# CMoy_breadboard.net
KiCad netlist of a schematic drawn in Altium Designer
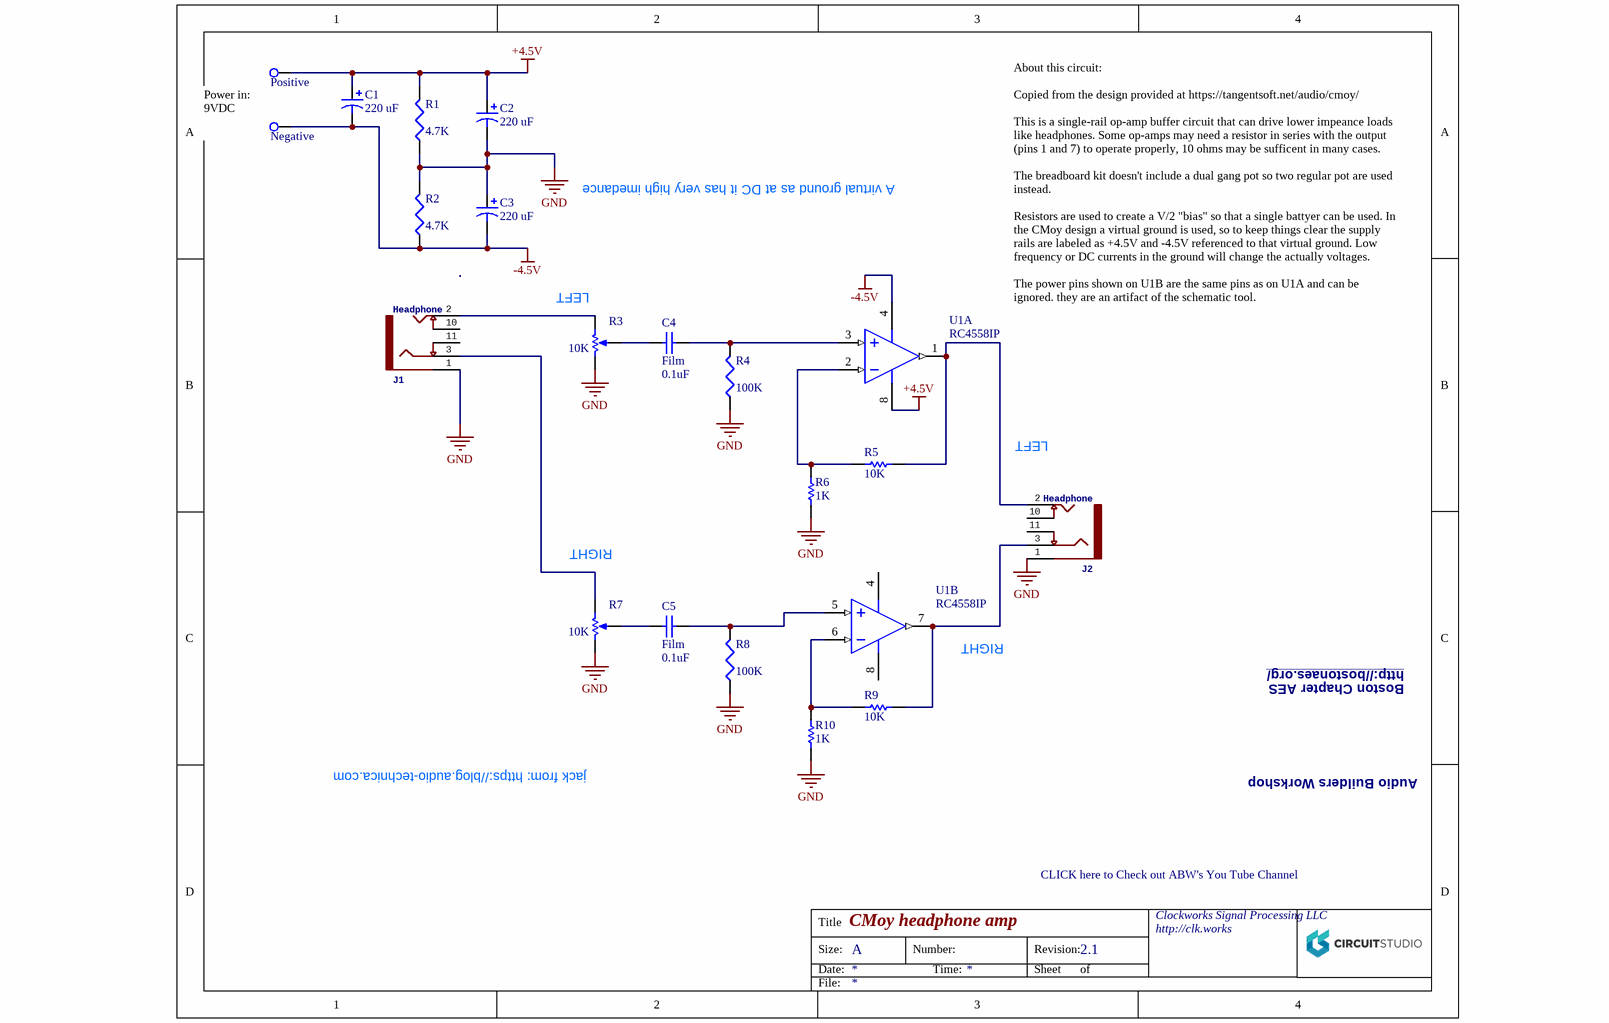
[diagram p0: CMoy.breadboard.SchDoc]

(export (version "E")
  (design (tool "Eeschema 10.0.6"))
  (components
    (comp (ref "C1")
      (value "220 uF")
      (footprint "RB7.6-15")
      (description "Polarized Capacitor (Radial)")
      (fields (field (name "Comment") "Cap Pol1") (field (name "PUBLISHER") "Altium Limited"))
      (libsource (lib "Miscellaneous Devices") (part "Cap Pol1"))
    )
    (comp (ref "C2")
      (value "220 uF")
      (footprint "RB7.6-15")
      (description "Polarized Capacitor (Radial)")
      (fields (field (name "Comment") "Cap Pol1") (field (name "PUBLISHER") "Altium Limited"))
      (libsource (lib "Miscellaneous Devices") (part "Cap Pol1"))
    )
    (comp (ref "C3")
      (value "220 uF")
      (footprint "RB7.6-15")
      (description "Polarized Capacitor (Radial)")
      (fields (field (name "Comment") "Cap Pol1") (field (name "PUBLISHER") "Altium Limited"))
      (libsource (lib "Miscellaneous Devices") (part "Cap Pol1"))
    )
    (comp (ref "C4")
      (value "Film")
      (footprint "RAD-0.3")
      (description "Capacitor")
      (fields (field (name "ALTIUM_VALUE") "0.1uF") (field (name "PUBLISHER") "Altium Limited"))
      (libsource (lib "Miscellaneous Devices") (part "Cap"))
    )
    (comp (ref "C5")
      (value "Film")
      (footprint "RAD-0.3")
      (description "Capacitor")
      (fields (field (name "ALTIUM_VALUE") "0.1uF") (field (name "PUBLISHER") "Altium Limited"))
      (libsource (lib "Miscellaneous Devices") (part "Cap"))
    )
    (comp (ref "J1")
      (value "Headphone")
      (footprint "SWITCHCRAFT_35RAPC4BHN2")
      (description "Conn 3.5MM Stereo Jack F 5 POS Solder RA Thru-Hole 5 Terminal 1 Port")
      (libsource (lib "CSP.J.connectors") (part "CSP-J0022-A"))
    )
    (comp (ref "J2")
      (value "Headphone")
      (footprint "SWITCHCRAFT_35RAPC4BHN2")
      (description "Conn 3.5MM Stereo Jack F 5 POS Solder RA Thru-Hole 5 Terminal 1 Port")
      (libsource (lib "") (part "CSP-J0022-A_1"))
    )
    (comp (ref "R1")
      (value "4.7K")
      (footprint "J1-0603")
      (description "Resistor")
      (fields (field (name "Comment") "Res3") (field (name "PUBLISHER") "Altium Limited"))
      (libsource (lib "Miscellaneous Devices") (part "Res3"))
    )
    (comp (ref "R2")
      (value "4.7K")
      (footprint "J1-0603")
      (description "Resistor")
      (fields (field (name "Comment") "Res3") (field (name "PUBLISHER") "Altium Limited"))
      (libsource (lib "Miscellaneous Devices") (part "Res3"))
    )
    (comp (ref "R3")
      (value "10K")
      (footprint "VR5")
      (description "Potentiometer")
      (fields (field (name "Comment") "RPot") (field (name "PUBLISHER") "Altium Limited"))
      (libsource (lib "Miscellaneous Devices") (part "RPot"))
    )
    (comp (ref "R4")
      (value "100K")
      (footprint "J1-0603")
      (description "Resistor")
      (fields (field (name "Comment") "Res3") (field (name "PUBLISHER") "Altium Limited"))
      (libsource (lib "Miscellaneous Devices") (part "Res3"))
    )
    (comp (ref "R5")
      (value "10K")
      (footprint "SL Axial 10k 1/4W")
      (description "10K 1/4W TH")
      (libsource (lib "met") (part "SL-R0020-A"))
    )
    (comp (ref "R6")
      (value "1K")
      (footprint "SL Axial 1k 1/4W")
      (description "1K 1/4W TH")
      (libsource (lib "met") (part "SL-R0016-A"))
    )
    (comp (ref "R7")
      (value "10K")
      (footprint "VR5")
      (description "Potentiometer")
      (fields (field (name "Comment") "RPot") (field (name "PUBLISHER") "Altium Limited"))
      (libsource (lib "Miscellaneous Devices") (part "RPot"))
    )
    (comp (ref "R8")
      (value "100K")
      (footprint "J1-0603")
      (description "Resistor")
      (fields (field (name "Comment") "Res3") (field (name "PUBLISHER") "Altium Limited"))
      (libsource (lib "Miscellaneous Devices") (part "Res3"))
    )
    (comp (ref "R9")
      (value "10K")
      (footprint "SL Axial 10k 1/4W")
      (description "10K 1/4W TH")
      (libsource (lib "met") (part "SL-R0020-A"))
    )
    (comp (ref "R10")
      (value "1K")
      (footprint "SL Axial 1k 1/4W")
      (description "1K 1/4W TH")
      (libsource (lib "met") (part "SL-R0016-A"))
    )
    (comp (ref "TP1")
      (value "Positive")
      (footprint "SL TEST POINT")
      (description "Connection point")
      (libsource (lib "met") (part "SL-X0005-A"))
    )
    (comp (ref "TP2")
      (value "Negative")
      (footprint "SL TEST POINT")
      (description "Connection point")
      (libsource (lib "met") (part "SL-X0005-A"))
    )
    (comp (ref "U1")
      (value "RC4558IP")
      (footprint "P0008A")
      (fields (field (name "MANUFACTURER") "Texas Instruments"))
      (libsource (lib "Altium Content Vault") (part "TI-AMP-D6-2-8_D"))
    )
  )
  (nets
    (net (code "1") (name "+4.5V") (class "Default")
      (node (ref "C1") (pin "1") (pinfunction "1_1") (pintype "passive"))
      (node (ref "C2") (pin "1") (pinfunction "1_1") (pintype "passive"))
      (node (ref "R1") (pin "2") (pinfunction "2_2") (pintype "passive"))
      (node (ref "TP1") (pin "1") (pinfunction "TP_1") (pintype "passive"))
      (node (ref "U1") (pin "8") (pinfunction "VCC+_8") (pintype "power_in"))
    )
    (net (code "2") (name "-4.5V") (class "Default")
      (node (ref "C1") (pin "2") (pinfunction "2_2") (pintype "passive"))
      (node (ref "C3") (pin "2") (pinfunction "2_2") (pintype "passive"))
      (node (ref "R2") (pin "1") (pinfunction "1_1") (pintype "passive"))
      (node (ref "TP2") (pin "1") (pinfunction "TP_1") (pintype "passive"))
      (node (ref "U1") (pin "4") (pinfunction "VCC-_4") (pintype "power_in"))
    )
    (net (code "3") (name "GND") (class "Default")
      (node (ref "C2") (pin "2") (pinfunction "2_2") (pintype "passive"))
      (node (ref "C3") (pin "1") (pinfunction "1_1") (pintype "passive"))
      (node (ref "J1") (pin "1") (pinfunction "SLEEVE_1") (pintype "passive"))
      (node (ref "J2") (pin "1") (pinfunction "SLEEVE_1") (pintype "passive"))
      (node (ref "R1") (pin "1") (pinfunction "1_1") (pintype "passive"))
      (node (ref "R10") (pin "1") (pinfunction "1_1") (pintype "passive"))
      (node (ref "R2") (pin "2") (pinfunction "2_2") (pintype "passive"))
      (node (ref "R3") (pin "2") (pinfunction "BOT_2") (pintype "passive"))
      (node (ref "R4") (pin "1") (pinfunction "1_1") (pintype "passive"))
      (node (ref "R6") (pin "1") (pinfunction "1_1") (pintype "passive"))
      (node (ref "R7") (pin "2") (pinfunction "BOT_2") (pintype "passive"))
      (node (ref "R8") (pin "1") (pinfunction "1_1") (pintype "passive"))
    )
    (net (code "4") (name "Net-(J1-RING)") (class "Default")
      (node (ref "J1") (pin "3") (pinfunction "RING_3") (pintype "passive"))
      (node (ref "R7") (pin "1") (pinfunction "TOP_1") (pintype "passive"))
    )
    (net (code "5") (name "Net-(J1-TIP)") (class "Default")
      (node (ref "J1") (pin "2") (pinfunction "TIP_2") (pintype "passive"))
      (node (ref "R3") (pin "1") (pinfunction "TOP_1") (pintype "passive"))
    )
    (net (code "6") (name "Net-(J2-RING)") (class "Default")
      (node (ref "J2") (pin "3") (pinfunction "RING_3") (pintype "passive"))
      (node (ref "R9") (pin "2") (pinfunction "2_2") (pintype "passive"))
      (node (ref "U1") (pin "7") (pinfunction "OUT2_7") (pintype "output"))
    )
    (net (code "7") (name "Net-(J2-TIP)") (class "Default")
      (node (ref "J2") (pin "2") (pinfunction "TIP_2") (pintype "passive"))
      (node (ref "R5") (pin "2") (pinfunction "2_2") (pintype "passive"))
      (node (ref "U1") (pin "1") (pinfunction "OUT1_1") (pintype "output"))
    )
    (net (code "8") (name "Net-(R3-TAP)") (class "Default")
      (node (ref "C4") (pin "1") (pinfunction "1_1") (pintype "passive"))
      (node (ref "R3") (pin "3") (pinfunction "TAP_3") (pintype "passive"))
    )
    (net (code "9") (name "Net-(R7-TAP)") (class "Default")
      (node (ref "C5") (pin "1") (pinfunction "1_1") (pintype "passive"))
      (node (ref "R7") (pin "3") (pinfunction "TAP_3") (pintype "passive"))
    )
    (net (code "10") (name "Net-(U1A-IN1+)") (class "Default")
      (node (ref "C4") (pin "2") (pinfunction "2_2") (pintype "passive"))
      (node (ref "R4") (pin "2") (pinfunction "2_2") (pintype "passive"))
      (node (ref "U1") (pin "3") (pinfunction "IN1+_3") (pintype "input"))
    )
    (net (code "11") (name "Net-(U1A-IN1-)") (class "Default")
      (node (ref "R5") (pin "1") (pinfunction "1_1") (pintype "passive"))
      (node (ref "R6") (pin "2") (pinfunction "2_2") (pintype "passive"))
      (node (ref "U1") (pin "2") (pinfunction "IN1-_2") (pintype "input"))
    )
    (net (code "12") (name "Net-(U1B-IN2+)") (class "Default")
      (node (ref "C5") (pin "2") (pinfunction "2_2") (pintype "passive"))
      (node (ref "R8") (pin "2") (pinfunction "2_2") (pintype "passive"))
      (node (ref "U1") (pin "5") (pinfunction "IN2+_5") (pintype "input"))
    )
    (net (code "13") (name "Net-(U1B-IN2-)") (class "Default")
      (node (ref "R10") (pin "2") (pinfunction "2_2") (pintype "passive"))
      (node (ref "R9") (pin "1") (pinfunction "1_1") (pintype "passive"))
      (node (ref "U1") (pin "6") (pinfunction "IN2-_6") (pintype "input"))
    )
    (net (code "14") (name "unconnected-(J1-RSH-Pad11)") (class "Default")
      (node (ref "J1") (pin "11") (pinfunction "RSH_11") (pintype "passive"))
    )
    (net (code "15") (name "unconnected-(J1-TSH-Pad10)") (class "Default")
      (node (ref "J1") (pin "10") (pinfunction "TSH_10") (pintype "passive"))
    )
    (net (code "16") (name "unconnected-(J2-RSH-Pad11)") (class "Default")
      (node (ref "J2") (pin "11") (pinfunction "RSH_11") (pintype "passive"))
    )
    (net (code "17") (name "unconnected-(J2-TSH-Pad10)") (class "Default")
      (node (ref "J2") (pin "10") (pinfunction "TSH_10") (pintype "passive"))
    )
    (net (code "18") (name "unconnected-(U1B-VCC+-Pad8)") (class "Default")
      (node (ref "U1") (pin "8") (pinfunction "VCC+_8") (pintype "power_in"))
    )
    (net (code "19") (name "unconnected-(U1B-VCC--Pad4)") (class "Default")
      (node (ref "U1") (pin "4") (pinfunction "VCC-_4") (pintype "power_in"))
    )
  )
)
